# mother_card_cs_956pm.net
KiCad netlist of a schematic drawn in EAGLE
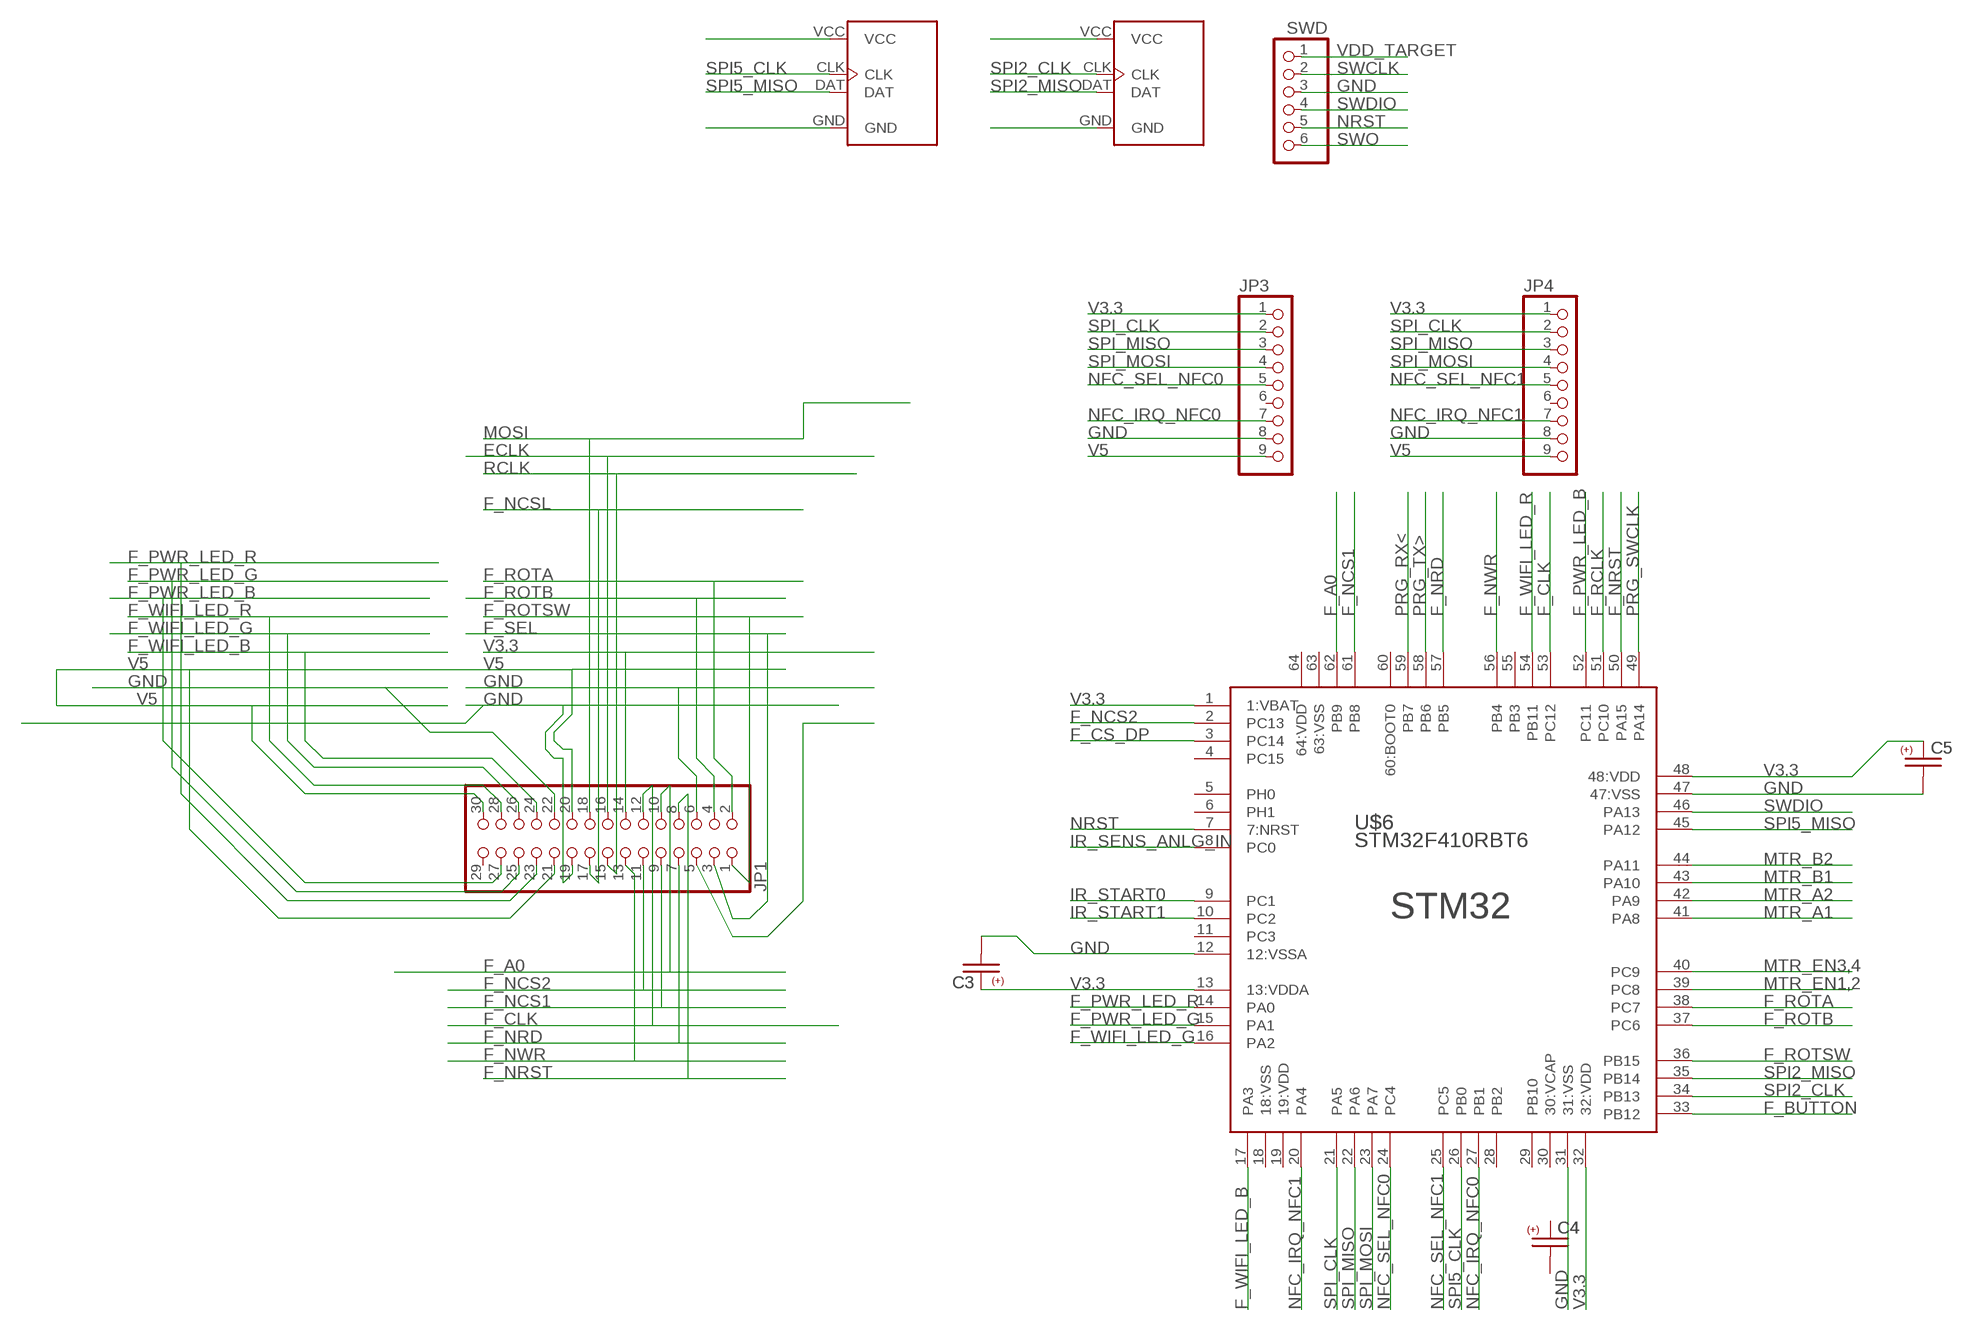
[diagram p0: schematic, sheet 1]
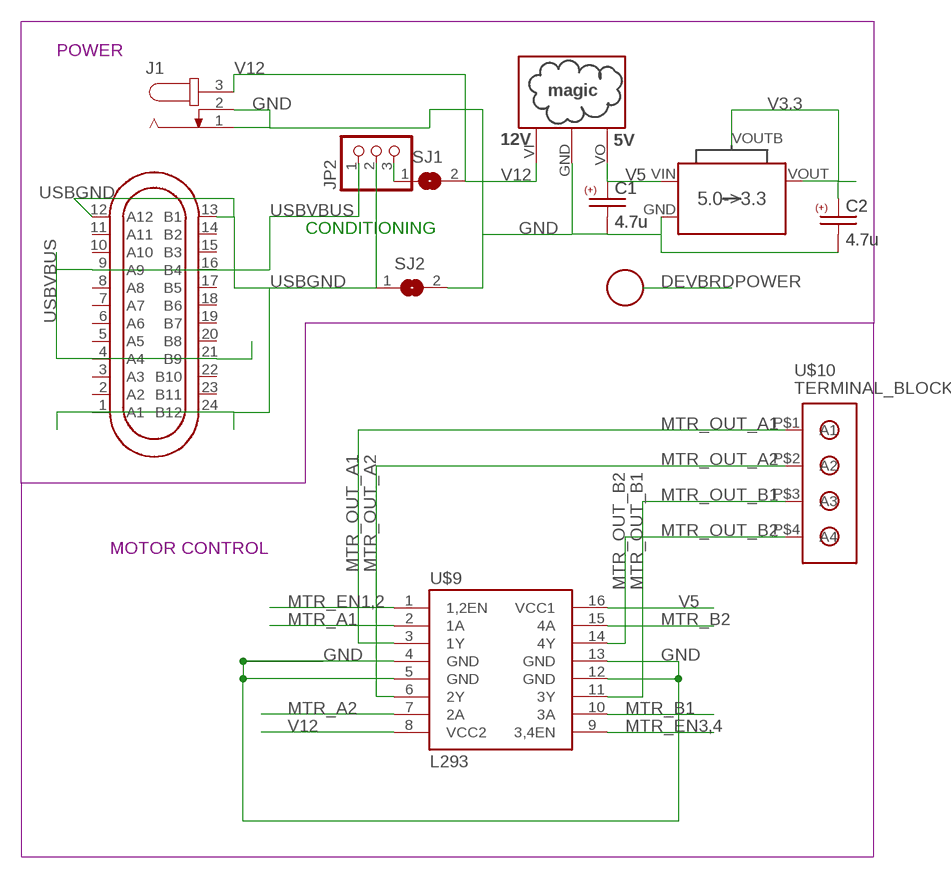
[diagram p1: schematic, sheet 2]

(export (version "E")
  (design (tool "Eeschema 10.0.6"))
  (components
    (comp (ref "C1")
      (value "4.7u")
      (footprint "eagle-import:C0805")
      (libsource (lib "eagle-import") (part "C-USC0805"))
    )
    (comp (ref "C2")
      (value "4.7u")
      (footprint "eagle-import:C0805")
      (libsource (lib "eagle-import") (part "C-USC0805"))
    )
    (comp (ref "J1")
      (value "JACK-PLUG0")
      (footprint "eagle-import:SPC4077")
      (libsource (lib "eagle-import") (part "JACK-PLUG0"))
    )
    (comp (ref "JP2")
      (value "PINHD-1X3")
      (footprint "eagle-import:1X03")
      (libsource (lib "eagle-import") (part "PINHD-1X3"))
    )
    (comp (ref "SJ1") (value "SJ") (footprint "eagle-import:SJ") (libsource (lib "eagle-import") (part "SJ")))
    (comp (ref "SJ2") (value "SJ") (footprint "eagle-import:SJ") (libsource (lib "eagle-import") (part "SJ")))
    (comp (ref "U$4")
      (value "OKI-78SR-W36")
      (footprint "eagle-import:SIP3")
      (libsource (lib "eagle-import") (part "OKI-78SR-W36"))
    )
    (comp (ref "U$7")
      (value "USB-C-BRKOUT")
      (footprint "eagle-import:USB-C-BRKOUT")
      (libsource (lib "eagle-import") (part "USB-C-BRKOUT"))
    )
    (comp (ref "U$8")
      (value "AP2114H")
      (footprint "eagle-import:AP2114H")
      (libsource (lib "eagle-import") (part "AP2114H"))
    )
    (comp (ref "U$9")
      (value "L293")
      (footprint "eagle-import:DIL16")
      (libsource (lib "eagle-import") (part "L293"))
    )
    (comp (ref "U$10")
      (value "TERMINAL_BLOCK")
      (footprint "eagle-import:1X4_BLOCK")
      (libsource (lib "eagle-import") (part "TERMINAL_BLOCK"))
    )
    (comp (ref "C3")
      (value "C-USC0805")
      (footprint "eagle-import:C0805")
      (libsource (lib "eagle-import") (part "C-USC0805"))
    )
    (comp (ref "C4")
      (value "C-USC0805")
      (footprint "eagle-import:C0805")
      (libsource (lib "eagle-import") (part "C-USC0805"))
    )
    (comp (ref "C5")
      (value "C-USC0805")
      (footprint "eagle-import:C0805")
      (libsource (lib "eagle-import") (part "C-USC0805"))
    )
    (comp (ref "JP1")
      (value "PINHD-2X15/SOCK")
      (footprint "eagle-import:2X15_SOCK")
      (libsource (lib "eagle-import") (part "PINHD-2X15/SOCK"))
    )
    (comp (ref "JP3")
      (value "PINHD-1X9/90")
      (footprint "eagle-import:1X09_90")
      (libsource (lib "eagle-import") (part "PINHD-1X9/90"))
    )
    (comp (ref "JP4")
      (value "PINHD-1X9/90")
      (footprint "eagle-import:1X09_90")
      (libsource (lib "eagle-import") (part "PINHD-1X9/90"))
    )
    (comp (ref "SWD")
      (value "PINHD-1X6")
      (footprint "eagle-import:1X06")
      (libsource (lib "eagle-import") (part "PINHD-1X6"))
    )
    (comp (ref "U$1")
      (value "HX711")
      (footprint "eagle-import:HX711")
      (libsource (lib "eagle-import") (part "HX711"))
    )
    (comp (ref "U$2")
      (value "HX711")
      (footprint "eagle-import:HX711")
      (libsource (lib "eagle-import") (part "HX711"))
    )
    (comp (ref "U$6")
      (value "STM32F410RBT6")
      (footprint "eagle-import:QFP50P1200X1200X160-64N")
      (libsource (lib "eagle-import") (part "STM32F410RBT6"))
    )
  )
  (nets
    (net (code "2") (name "ECLK") (class "Default")
      (node (ref "JP1") (pin "16") (pinfunction "16_16") (pintype "passive"))
    )
    (net (code "3") (name "F_A0") (class "Default")
      (node (ref "JP1") (pin "10") (pinfunction "10_10") (pintype "passive"))
      (node (ref "U$6") (pin "62") (pinfunction "PB9_62") (pintype "bidirectional"))
    )
    (net (code "4") (name "F_BUTTON") (class "Default")
      (node (ref "U$6") (pin "33") (pinfunction "PB12_33") (pintype "bidirectional"))
    )
    (net (code "5") (name "F_CLK") (class "Default")
      (node (ref "JP1") (pin "12") (pinfunction "12_12") (pintype "passive"))
      (node (ref "U$6") (pin "53") (pinfunction "PC12_53") (pintype "bidirectional"))
    )
    (net (code "6") (name "F_CS_DP") (class "Default")
      (node (ref "U$6") (pin "3") (pinfunction "PC14_3") (pintype "bidirectional"))
    )
    (net (code "7") (name "F_NCS1") (class "Default")
      (node (ref "JP1") (pin "9") (pinfunction "9_9") (pintype "passive"))
      (node (ref "U$6") (pin "61") (pinfunction "PB8_61") (pintype "bidirectional"))
    )
    (net (code "8") (name "F_NCS2") (class "Default")
      (node (ref "JP1") (pin "11") (pinfunction "11_11") (pintype "passive"))
      (node (ref "U$6") (pin "2") (pinfunction "PC13_2") (pintype "bidirectional"))
    )
    (net (code "9") (name "F_NCSL") (class "Default")
      (node (ref "JP1") (pin "17") (pinfunction "17_17") (pintype "passive"))
    )
    (net (code "10") (name "F_NRD") (class "Default")
      (node (ref "JP1") (pin "7") (pinfunction "7_7") (pintype "passive"))
      (node (ref "U$6") (pin "57") (pinfunction "PB5_57") (pintype "bidirectional"))
    )
    (net (code "11") (name "F_NRST") (class "Default")
      (node (ref "JP1") (pin "8") (pinfunction "8_8") (pintype "passive"))
      (node (ref "U$6") (pin "50") (pinfunction "PA15_50") (pintype "bidirectional"))
    )
    (net (code "12") (name "F_NWR") (class "Default")
      (node (ref "JP1") (pin "13") (pinfunction "13_13") (pintype "passive"))
      (node (ref "U$6") (pin "56") (pinfunction "PB4_56") (pintype "bidirectional"))
    )
    (net (code "13") (name "F_PWR_LED_B") (class "Default")
      (node (ref "JP1") (pin "27") (pinfunction "27_27") (pintype "passive"))
      (node (ref "U$6") (pin "52") (pinfunction "PC11_52") (pintype "bidirectional"))
    )
    (net (code "14") (name "F_PWR_LED_G") (class "Default")
      (node (ref "JP1") (pin "25") (pinfunction "25_25") (pintype "passive"))
      (node (ref "U$6") (pin "15") (pinfunction "PA1_15") (pintype "bidirectional"))
    )
    (net (code "15") (name "F_PWR_LED_R") (class "Default")
      (node (ref "JP1") (pin "23") (pinfunction "23_23") (pintype "passive"))
      (node (ref "U$6") (pin "14") (pinfunction "PA0_14") (pintype "bidirectional"))
    )
    (net (code "16") (name "F_RCLK") (class "Default")
      (node (ref "U$6") (pin "51") (pinfunction "PC10_51") (pintype "bidirectional"))
    )
    (net (code "17") (name "F_ROTA") (class "Default")
      (node (ref "JP1") (pin "2") (pinfunction "2_2") (pintype "passive"))
      (node (ref "U$6") (pin "38") (pinfunction "PC7_38") (pintype "bidirectional"))
    )
    (net (code "18") (name "F_ROTB") (class "Default")
      (node (ref "JP1") (pin "4") (pinfunction "4_4") (pintype "passive"))
      (node (ref "U$6") (pin "37") (pinfunction "PC6_37") (pintype "bidirectional"))
    )
    (net (code "19") (name "F_ROTSW") (class "Default")
      (node (ref "JP1") (pin "1") (pinfunction "1_1") (pintype "passive"))
      (node (ref "U$6") (pin "36") (pinfunction "PB15_36") (pintype "bidirectional"))
    )
    (net (code "20") (name "F_SEL") (class "Default")
      (node (ref "JP1") (pin "3") (pinfunction "3_3") (pintype "passive"))
    )
    (net (code "21") (name "F_WIFI_LED_B") (class "Default")
      (node (ref "JP1") (pin "24") (pinfunction "24_24") (pintype "passive"))
      (node (ref "U$6") (pin "17") (pinfunction "PA3_17") (pintype "bidirectional"))
    )
    (net (code "22") (name "F_WIFI_LED_G") (class "Default")
      (node (ref "JP1") (pin "26") (pinfunction "26_26") (pintype "passive"))
      (node (ref "U$6") (pin "16") (pinfunction "PA2_16") (pintype "bidirectional"))
    )
    (net (code "23") (name "F_WIFI_LED_R") (class "Default")
      (node (ref "JP1") (pin "28") (pinfunction "28_28") (pintype "passive"))
      (node (ref "U$6") (pin "54") (pinfunction "PB11_54") (pintype "bidirectional"))
    )
    (net (code "24") (name "GND") (class "Default")
      (node (ref "C1") (pin "2") (pinfunction "2_2") (pintype "passive"))
      (node (ref "C2") (pin "2") (pinfunction "2_2") (pintype "passive"))
      (node (ref "C3") (pin "2") (pinfunction "2_2") (pintype "passive"))
      (node (ref "C5") (pin "2") (pinfunction "2_2") (pintype "passive"))
      (node (ref "J1") (pin "1") (pinfunction "1_1") (pintype "passive"))
      (node (ref "J1") (pin "2") (pinfunction "2_2") (pintype "passive"))
      (node (ref "JP1") (pin "19") (pinfunction "19_19") (pintype "passive"))
      (node (ref "JP1") (pin "22") (pinfunction "22_22") (pintype "passive"))
      (node (ref "JP1") (pin "6") (pinfunction "6_6") (pintype "passive"))
      (node (ref "JP3") (pin "8") (pinfunction "8_8") (pintype "passive"))
      (node (ref "JP4") (pin "8") (pinfunction "8_8") (pintype "passive"))
      (node (ref "SJ2") (pin "2") (pinfunction "2_2") (pintype "passive"))
      (node (ref "SWD") (pin "3") (pinfunction "3_3") (pintype "passive"))
      (node (ref "U$4") (pin "GND") (pinfunction "P$2_GND") (pintype "power_in"))
      (node (ref "U$6") (pin "12") (pinfunction "12:VSSA_12") (pintype "bidirectional"))
      (node (ref "U$6") (pin "31") (pinfunction "31:VSS_31") (pintype "bidirectional"))
      (node (ref "U$6") (pin "47") (pinfunction "47:VSS_47") (pintype "bidirectional"))
      (node (ref "U$8") (pin "GND") (pinfunction "GND_GND") (pintype "power_in"))
      (node (ref "U$9") (pin "12") (pinfunction "GND_12") (pintype "bidirectional"))
      (node (ref "U$9") (pin "13") (pinfunction "GND_13") (pintype "bidirectional"))
      (node (ref "U$9") (pin "4") (pinfunction "GND_4") (pintype "bidirectional"))
      (node (ref "U$9") (pin "5") (pinfunction "GND_5") (pintype "bidirectional"))
    )
    (net (code "25") (name "IR_SENS_ANLG_IN") (class "Default")
      (node (ref "U$6") (pin "8") (pinfunction "PC0_8") (pintype "bidirectional"))
    )
    (net (code "26") (name "IR_START0") (class "Default")
      (node (ref "U$6") (pin "9") (pinfunction "PC1_9") (pintype "bidirectional"))
    )
    (net (code "27") (name "IR_START1") (class "Default")
      (node (ref "U$6") (pin "10") (pinfunction "PC2_10") (pintype "bidirectional"))
    )
    (net (code "28") (name "MOSI") (class "Default")
      (node (ref "JP1") (pin "18") (pinfunction "18_18") (pintype "passive"))
    )
    (net (code "29") (name "MTR_A1") (class "Default")
      (node (ref "U$6") (pin "41") (pinfunction "PA8_41") (pintype "bidirectional"))
      (node (ref "U$9") (pin "2") (pinfunction "1A_2") (pintype "bidirectional"))
    )
    (net (code "30") (name "MTR_A2") (class "Default")
      (node (ref "U$6") (pin "42") (pinfunction "PA9_42") (pintype "bidirectional"))
      (node (ref "U$9") (pin "7") (pinfunction "2A_7") (pintype "bidirectional"))
    )
    (net (code "31") (name "MTR_B1") (class "Default")
      (node (ref "U$6") (pin "43") (pinfunction "PA10_43") (pintype "bidirectional"))
      (node (ref "U$9") (pin "10") (pinfunction "3A_10") (pintype "bidirectional"))
    )
    (net (code "32") (name "MTR_B2") (class "Default")
      (node (ref "U$6") (pin "44") (pinfunction "PA11_44") (pintype "bidirectional"))
      (node (ref "U$9") (pin "15") (pinfunction "4A_15") (pintype "bidirectional"))
    )
    (net (code "33") (name "MTR_EN1,2") (class "Default")
      (node (ref "U$6") (pin "39") (pinfunction "PC8_39") (pintype "bidirectional"))
      (node (ref "U$9") (pin "1") (pinfunction "1,2EN_1") (pintype "bidirectional"))
    )
    (net (code "34") (name "MTR_EN3,4") (class "Default")
      (node (ref "U$6") (pin "40") (pinfunction "PC9_40") (pintype "bidirectional"))
      (node (ref "U$9") (pin "9") (pinfunction "3,4EN_9") (pintype "bidirectional"))
    )
    (net (code "35") (name "MTR_OUT_A1") (class "Default")
      (node (ref "U$10") (pin "P$1") (pinfunction "A1_P$1") (pintype "bidirectional"))
      (node (ref "U$9") (pin "3") (pinfunction "1Y_3") (pintype "bidirectional"))
    )
    (net (code "36") (name "MTR_OUT_A2") (class "Default")
      (node (ref "U$10") (pin "P$2") (pinfunction "A2_P$2") (pintype "bidirectional"))
      (node (ref "U$9") (pin "6") (pinfunction "2Y_6") (pintype "bidirectional"))
    )
    (net (code "37") (name "MTR_OUT_B1") (class "Default")
      (node (ref "U$10") (pin "P$3") (pinfunction "A3_P$3") (pintype "bidirectional"))
      (node (ref "U$9") (pin "11") (pinfunction "3Y_11") (pintype "bidirectional"))
    )
    (net (code "38") (name "MTR_OUT_B2") (class "Default")
      (node (ref "U$10") (pin "P$4") (pinfunction "A4_P$4") (pintype "bidirectional"))
      (node (ref "U$9") (pin "14") (pinfunction "4Y_14") (pintype "bidirectional"))
    )
    (net (code "39") (name "NFC_IRQ_NFC0") (class "Default")
      (node (ref "JP3") (pin "7") (pinfunction "7_7") (pintype "passive"))
      (node (ref "U$6") (pin "27") (pinfunction "PB1_27") (pintype "bidirectional"))
    )
    (net (code "40") (name "NFC_IRQ_NFC1") (class "Default")
      (node (ref "JP4") (pin "7") (pinfunction "7_7") (pintype "passive"))
      (node (ref "U$6") (pin "20") (pinfunction "PA4_20") (pintype "bidirectional"))
    )
    (net (code "41") (name "NFC_SEL_NFC0") (class "Default")
      (node (ref "JP3") (pin "5") (pinfunction "5_5") (pintype "passive"))
      (node (ref "U$6") (pin "24") (pinfunction "PC4_24") (pintype "bidirectional"))
    )
    (net (code "42") (name "NFC_SEL_NFC1") (class "Default")
      (node (ref "JP4") (pin "5") (pinfunction "5_5") (pintype "passive"))
      (node (ref "U$6") (pin "25") (pinfunction "PC5_25") (pintype "bidirectional"))
    )
    (net (code "43") (name "NRST") (class "Default")
      (node (ref "SWD") (pin "5") (pinfunction "5_5") (pintype "passive"))
      (node (ref "U$6") (pin "7") (pinfunction "7:NRST_7") (pintype "bidirectional"))
    )
    (net (code "44") (name "Net-(JP2-Pad3)") (class "Default")
      (node (ref "JP2") (pin "3") (pinfunction "3_3") (pintype "passive"))
      (node (ref "SJ1") (pin "1") (pinfunction "1_1") (pintype "passive"))
    )
    (net (code "45") (name "PRG_RX<") (class "Default")
      (node (ref "U$6") (pin "59") (pinfunction "PB7_59") (pintype "bidirectional"))
    )
    (net (code "46") (name "PRG_SWCLK") (class "Default")
      (node (ref "U$6") (pin "49") (pinfunction "PA14_49") (pintype "bidirectional"))
    )
    (net (code "47") (name "PRG_TX>") (class "Default")
      (node (ref "U$6") (pin "58") (pinfunction "PB6_58") (pintype "bidirectional"))
    )
    (net (code "48") (name "RCLK") (class "Default")
      (node (ref "JP1") (pin "15") (pinfunction "15_15") (pintype "passive"))
    )
    (net (code "49") (name "SPI2_CLK") (class "Default")
      (node (ref "U$2") (pin "CLK") (pinfunction "CLK_CLK") (pintype "bidirectional"))
      (node (ref "U$6") (pin "34") (pinfunction "PB13_34") (pintype "bidirectional"))
    )
    (net (code "50") (name "SPI2_MISO") (class "Default")
      (node (ref "U$2") (pin "DAT") (pinfunction "DAT_DAT") (pintype "bidirectional"))
      (node (ref "U$6") (pin "35") (pinfunction "PB14_35") (pintype "bidirectional"))
    )
    (net (code "51") (name "SPI5_CLK") (class "Default")
      (node (ref "U$1") (pin "CLK") (pinfunction "CLK_CLK") (pintype "bidirectional"))
      (node (ref "U$6") (pin "26") (pinfunction "PB0_26") (pintype "bidirectional"))
    )
    (net (code "52") (name "SPI5_MISO") (class "Default")
      (node (ref "U$1") (pin "DAT") (pinfunction "DAT_DAT") (pintype "bidirectional"))
      (node (ref "U$6") (pin "45") (pinfunction "PA12_45") (pintype "bidirectional"))
    )
    (net (code "53") (name "SPI_CLK") (class "Default")
      (node (ref "JP3") (pin "2") (pinfunction "2_2") (pintype "passive"))
      (node (ref "JP4") (pin "2") (pinfunction "2_2") (pintype "passive"))
      (node (ref "U$6") (pin "21") (pinfunction "PA5_21") (pintype "bidirectional"))
    )
    (net (code "54") (name "SPI_MISO") (class "Default")
      (node (ref "JP3") (pin "3") (pinfunction "3_3") (pintype "passive"))
      (node (ref "JP4") (pin "3") (pinfunction "3_3") (pintype "passive"))
      (node (ref "U$6") (pin "22") (pinfunction "PA6_22") (pintype "bidirectional"))
    )
    (net (code "55") (name "SPI_MOSI") (class "Default")
      (node (ref "JP3") (pin "4") (pinfunction "4_4") (pintype "passive"))
      (node (ref "JP4") (pin "4") (pinfunction "4_4") (pintype "passive"))
      (node (ref "U$6") (pin "23") (pinfunction "PA7_23") (pintype "bidirectional"))
    )
    (net (code "56") (name "SWCLK") (class "Default")
      (node (ref "SWD") (pin "2") (pinfunction "2_2") (pintype "passive"))
    )
    (net (code "57") (name "SWDIO") (class "Default")
      (node (ref "SWD") (pin "4") (pinfunction "4_4") (pintype "passive"))
      (node (ref "U$6") (pin "46") (pinfunction "PA13_46") (pintype "bidirectional"))
    )
    (net (code "58") (name "SWO") (class "Default")
      (node (ref "SWD") (pin "6") (pinfunction "6_6") (pintype "passive"))
    )
    (net (code "59") (name "USBGND") (class "Default")
      (node (ref "JP2") (pin "2") (pinfunction "2_2") (pintype "passive"))
      (node (ref "SJ2") (pin "1") (pinfunction "1_1") (pintype "passive"))
      (node (ref "U$7") (pin "1") (pinfunction "A1_1") (pintype "bidirectional"))
      (node (ref "U$7") (pin "12") (pinfunction "A12_12") (pintype "bidirectional"))
      (node (ref "U$7") (pin "13") (pinfunction "B1_13") (pintype "bidirectional"))
      (node (ref "U$7") (pin "24") (pinfunction "B12_24") (pintype "bidirectional"))
    )
    (net (code "60") (name "USBVBUS") (class "Default")
      (node (ref "JP2") (pin "1") (pinfunction "1_1") (pintype "passive"))
      (node (ref "U$7") (pin "16") (pinfunction "B4_16") (pintype "bidirectional"))
      (node (ref "U$7") (pin "21") (pinfunction "B9_21") (pintype "bidirectional"))
      (node (ref "U$7") (pin "4") (pinfunction "A4_4") (pintype "bidirectional"))
      (node (ref "U$7") (pin "9") (pinfunction "A9_9") (pintype "bidirectional"))
    )
    (net (code "61") (name "V3.3") (class "Default")
      (node (ref "C2") (pin "1") (pinfunction "1_1") (pintype "passive"))
      (node (ref "C3") (pin "1") (pinfunction "1_1") (pintype "passive"))
      (node (ref "C5") (pin "1") (pinfunction "1_1") (pintype "passive"))
      (node (ref "JP1") (pin "14") (pinfunction "14_14") (pintype "passive"))
      (node (ref "JP3") (pin "1") (pinfunction "1_1") (pintype "passive"))
      (node (ref "JP4") (pin "1") (pinfunction "1_1") (pintype "passive"))
      (node (ref "U$6") (pin "1") (pinfunction "1:VBAT_1") (pintype "bidirectional"))
      (node (ref "U$6") (pin "13") (pinfunction "13:VDDA_13") (pintype "bidirectional"))
      (node (ref "U$6") (pin "32") (pinfunction "32:VDD_32") (pintype "bidirectional"))
      (node (ref "U$6") (pin "48") (pinfunction "48:VDD_48") (pintype "bidirectional"))
      (node (ref "U$8") (pin "VOUT") (pinfunction "VO_VOUT") (pintype "output"))
      (node (ref "U$8") (pin "VOUTB") (pinfunction "BODY_VOUTB") (pintype "open_collector"))
    )
    (net (code "62") (name "V5") (class "Default")
      (node (ref "C1") (pin "1") (pinfunction "1_1") (pintype "passive"))
      (node (ref "JP1") (pin "20") (pinfunction "20_20") (pintype "passive"))
      (node (ref "JP1") (pin "21") (pinfunction "21_21") (pintype "passive"))
      (node (ref "JP1") (pin "30") (pinfunction "30_30") (pintype "passive"))
      (node (ref "JP3") (pin "9") (pinfunction "9_9") (pintype "passive"))
      (node (ref "JP4") (pin "9") (pinfunction "9_9") (pintype "passive"))
      (node (ref "U$4") (pin "VO") (pinfunction "P$3_VO") (pintype "output"))
      (node (ref "U$8") (pin "VIN") (pinfunction "VI_VIN") (pintype "input"))
      (node (ref "U$9") (pin "16") (pinfunction "VCC1_16") (pintype "bidirectional"))
    )
    (net (code "63") (name "V12") (class "Default")
      (node (ref "J1") (pin "3") (pinfunction "3_3") (pintype "passive"))
      (node (ref "SJ1") (pin "2") (pinfunction "2_2") (pintype "passive"))
      (node (ref "U$4") (pin "VI") (pinfunction "P$1_VI") (pintype "input"))
      (node (ref "U$9") (pin "8") (pinfunction "VCC2_8") (pintype "bidirectional"))
    )
    (net (code "64") (name "VDD_TARGET") (class "Default")
      (node (ref "SWD") (pin "1") (pinfunction "1_1") (pintype "passive"))
    )
    (net (code "65") (name "unconnected-(C4-Pad1)") (class "Default")
      (node (ref "C4") (pin "1") (pinfunction "1_1") (pintype "passive"))
    )
    (net (code "66") (name "unconnected-(C4-Pad2)") (class "Default")
      (node (ref "C4") (pin "2") (pinfunction "2_2") (pintype "passive"))
    )
    (net (code "67") (name "unconnected-(JP1-Pad5)") (class "Default")
      (node (ref "JP1") (pin "5") (pinfunction "5_5") (pintype "passive"))
    )
    (net (code "68") (name "unconnected-(JP1-Pad29)") (class "Default")
      (node (ref "JP1") (pin "29") (pinfunction "29_29") (pintype "passive"))
    )
    (net (code "69") (name "unconnected-(JP3-Pad6)") (class "Default")
      (node (ref "JP3") (pin "6") (pinfunction "6_6") (pintype "passive"))
    )
    (net (code "70") (name "unconnected-(JP4-Pad6)") (class "Default")
      (node (ref "JP4") (pin "6") (pinfunction "6_6") (pintype "passive"))
    )
    (net (code "71") (name "unconnected-(U$1-PadGND)") (class "Default")
      (node (ref "U$1") (pin "GND") (pinfunction "GND_GND") (pintype "power_in"))
    )
    (net (code "72") (name "unconnected-(U$1-PadVCC)") (class "Default")
      (node (ref "U$1") (pin "VCC") (pinfunction "VCC_VCC") (pintype "power_in"))
    )
    (net (code "73") (name "unconnected-(U$2-PadGND)") (class "Default")
      (node (ref "U$2") (pin "GND") (pinfunction "GND_GND") (pintype "power_in"))
    )
    (net (code "74") (name "unconnected-(U$2-PadVCC)") (class "Default")
      (node (ref "U$2") (pin "VCC") (pinfunction "VCC_VCC") (pintype "power_in"))
    )
    (net (code "75") (name "unconnected-(U$6-18:VSS-Pad18)") (class "Default")
      (node (ref "U$6") (pin "18") (pinfunction "18:VSS_18") (pintype "bidirectional"))
    )
    (net (code "76") (name "unconnected-(U$6-19:VDD-Pad19)") (class "Default")
      (node (ref "U$6") (pin "19") (pinfunction "19:VDD_19") (pintype "bidirectional"))
    )
    (net (code "77") (name "unconnected-(U$6-30:VCAP-Pad30)") (class "Default")
      (node (ref "U$6") (pin "30") (pinfunction "30:VCAP_30") (pintype "bidirectional"))
    )
    (net (code "78") (name "unconnected-(U$6-60:BOOT0-Pad60)") (class "Default")
      (node (ref "U$6") (pin "60") (pinfunction "60:BOOT0_60") (pintype "bidirectional"))
    )
    (net (code "79") (name "unconnected-(U$6-63:VSS-Pad63)") (class "Default")
      (node (ref "U$6") (pin "63") (pinfunction "63:VSS_63") (pintype "bidirectional"))
    )
    (net (code "80") (name "unconnected-(U$6-64:VDD-Pad64)") (class "Default")
      (node (ref "U$6") (pin "64") (pinfunction "64:VDD_64") (pintype "bidirectional"))
    )
    (net (code "81") (name "unconnected-(U$6-PB2-Pad28)") (class "Default")
      (node (ref "U$6") (pin "28") (pinfunction "PB2_28") (pintype "bidirectional"))
    )
    (net (code "82") (name "unconnected-(U$6-PB3-Pad55)") (class "Default")
      (node (ref "U$6") (pin "55") (pinfunction "PB3_55") (pintype "bidirectional"))
    )
    (net (code "83") (name "unconnected-(U$6-PB10-Pad29)") (class "Default")
      (node (ref "U$6") (pin "29") (pinfunction "PB10_29") (pintype "bidirectional"))
    )
    (net (code "84") (name "unconnected-(U$6-PC3-Pad11)") (class "Default")
      (node (ref "U$6") (pin "11") (pinfunction "PC3_11") (pintype "bidirectional"))
    )
    (net (code "85") (name "unconnected-(U$6-PC15-Pad4)") (class "Default")
      (node (ref "U$6") (pin "4") (pinfunction "PC15_4") (pintype "bidirectional"))
    )
    (net (code "86") (name "unconnected-(U$6-PH0-Pad5)") (class "Default")
      (node (ref "U$6") (pin "5") (pinfunction "PH0_5") (pintype "bidirectional"))
    )
    (net (code "87") (name "unconnected-(U$6-PH1-Pad6)") (class "Default")
      (node (ref "U$6") (pin "6") (pinfunction "PH1_6") (pintype "bidirectional"))
    )
    (net (code "88") (name "unconnected-(U$7-A2-Pad2)") (class "Default")
      (node (ref "U$7") (pin "2") (pinfunction "A2_2") (pintype "bidirectional"))
    )
    (net (code "89") (name "unconnected-(U$7-A3-Pad3)") (class "Default")
      (node (ref "U$7") (pin "3") (pinfunction "A3_3") (pintype "bidirectional"))
    )
    (net (code "90") (name "unconnected-(U$7-A5-Pad5)") (class "Default")
      (node (ref "U$7") (pin "5") (pinfunction "A5_5") (pintype "bidirectional"))
    )
    (net (code "91") (name "unconnected-(U$7-A6-Pad6)") (class "Default")
      (node (ref "U$7") (pin "6") (pinfunction "A6_6") (pintype "bidirectional"))
    )
    (net (code "92") (name "unconnected-(U$7-A7-Pad7)") (class "Default")
      (node (ref "U$7") (pin "7") (pinfunction "A7_7") (pintype "bidirectional"))
    )
    (net (code "93") (name "unconnected-(U$7-A8-Pad8)") (class "Default")
      (node (ref "U$7") (pin "8") (pinfunction "A8_8") (pintype "bidirectional"))
    )
    (net (code "94") (name "unconnected-(U$7-A10-Pad10)") (class "Default")
      (node (ref "U$7") (pin "10") (pinfunction "A10_10") (pintype "bidirectional"))
    )
    (net (code "95") (name "unconnected-(U$7-A11-Pad11)") (class "Default")
      (node (ref "U$7") (pin "11") (pinfunction "A11_11") (pintype "bidirectional"))
    )
    (net (code "96") (name "unconnected-(U$7-B2-Pad14)") (class "Default")
      (node (ref "U$7") (pin "14") (pinfunction "B2_14") (pintype "bidirectional"))
    )
    (net (code "97") (name "unconnected-(U$7-B3-Pad15)") (class "Default")
      (node (ref "U$7") (pin "15") (pinfunction "B3_15") (pintype "bidirectional"))
    )
    (net (code "98") (name "unconnected-(U$7-B5-Pad17)") (class "Default")
      (node (ref "U$7") (pin "17") (pinfunction "B5_17") (pintype "bidirectional"))
    )
    (net (code "99") (name "unconnected-(U$7-B6-Pad18)") (class "Default")
      (node (ref "U$7") (pin "18") (pinfunction "B6_18") (pintype "bidirectional"))
    )
    (net (code "100") (name "unconnected-(U$7-B7-Pad19)") (class "Default")
      (node (ref "U$7") (pin "19") (pinfunction "B7_19") (pintype "bidirectional"))
    )
    (net (code "101") (name "unconnected-(U$7-B8-Pad20)") (class "Default")
      (node (ref "U$7") (pin "20") (pinfunction "B8_20") (pintype "bidirectional"))
    )
    (net (code "102") (name "unconnected-(U$7-B10-Pad22)") (class "Default")
      (node (ref "U$7") (pin "22") (pinfunction "B10_22") (pintype "bidirectional"))
    )
    (net (code "103") (name "unconnected-(U$7-B11-Pad23)") (class "Default")
      (node (ref "U$7") (pin "23") (pinfunction "B11_23") (pintype "bidirectional"))
    )
  )
)
